# mp3thing_simple1.net
KiCad netlist of a schematic drawn in EAGLE
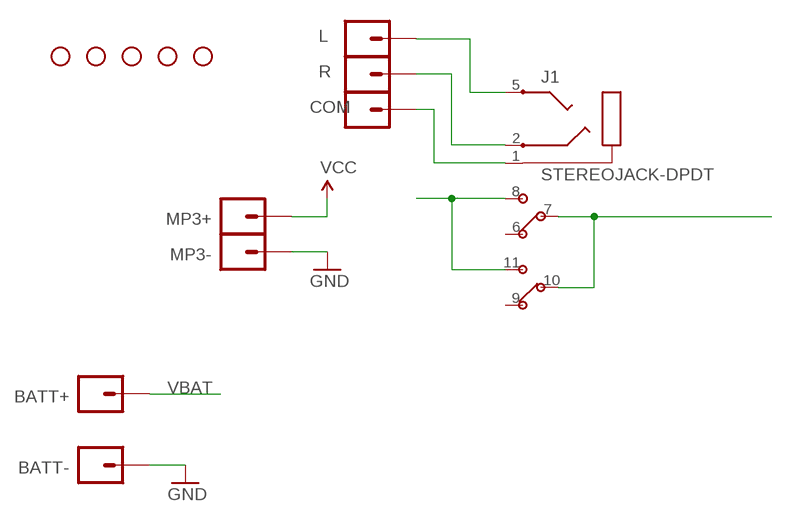
[diagram p0: schematic, sheet 1]

(export (version "E")
  (design (tool "Eeschema 10.0.6"))
  (components
    (comp (ref "BATT+")
      (value "M01PTH")
      (footprint "eagle-import:1X01")
      (libsource (lib "eagle-import") (part "M01PTH"))
    )
    (comp (ref "BATT-")
      (value "M01PTH")
      (footprint "eagle-import:1X01")
      (libsource (lib "eagle-import") (part "M01PTH"))
    )
    (comp (ref "COM")
      (value "M01PTH")
      (footprint "eagle-import:1X01")
      (libsource (lib "eagle-import") (part "M01PTH"))
    )
    (comp (ref "J1")
      (value "STEREOJACK-DPDT")
      (footprint "eagle-import:STX3100-9C")
      (libsource (lib "eagle-import") (part "STEREOJACK-DPDT"))
    )
    (comp (ref "JP1")
      (value "STAND-OFF")
      (footprint "eagle-import:STAND-OFF")
      (libsource (lib "eagle-import") (part "STAND-OFF"))
    )
    (comp (ref "JP2")
      (value "STAND-OFF")
      (footprint "eagle-import:STAND-OFF")
      (libsource (lib "eagle-import") (part "STAND-OFF"))
    )
    (comp (ref "JP3")
      (value "STAND-OFF")
      (footprint "eagle-import:STAND-OFF")
      (libsource (lib "eagle-import") (part "STAND-OFF"))
    )
    (comp (ref "JP4")
      (value "STAND-OFF")
      (footprint "eagle-import:STAND-OFF")
      (libsource (lib "eagle-import") (part "STAND-OFF"))
    )
    (comp (ref "JP5")
      (value "STAND-OFF")
      (footprint "eagle-import:STAND-OFF")
      (libsource (lib "eagle-import") (part "STAND-OFF"))
    )
    (comp (ref "L")
      (value "M01PTH")
      (footprint "eagle-import:1X01")
      (libsource (lib "eagle-import") (part "M01PTH"))
    )
    (comp (ref "MP3+")
      (value "M01PTH")
      (footprint "eagle-import:1X01")
      (libsource (lib "eagle-import") (part "M01PTH"))
    )
    (comp (ref "MP3-")
      (value "M01PTH")
      (footprint "eagle-import:1X01")
      (libsource (lib "eagle-import") (part "M01PTH"))
    )
    (comp (ref "R")
      (value "M01PTH")
      (footprint "eagle-import:1X01")
      (libsource (lib "eagle-import") (part "M01PTH"))
    )
  )
  (nets
    (net (code "1") (name "/VBAT") (class "Default")
      (node (ref "BATT+") (pin "1") (pinfunction "1_1") (pintype "passive"))
      (node (ref "J1") (pin "10") (pinfunction "10_10") (pintype "passive"))
      (node (ref "J1") (pin "7") (pinfunction "7_7") (pintype "passive"))
    )
    (net (code "2") (name "GND") (class "Default")
      (node (ref "BATT-") (pin "1") (pinfunction "1_1") (pintype "passive"))
      (node (ref "MP3-") (pin "1") (pinfunction "1_1") (pintype "passive"))
    )
    (net (code "3") (name "Net-(COM-Pad1)") (class "Default")
      (node (ref "COM") (pin "1") (pinfunction "1_1") (pintype "passive"))
      (node (ref "J1") (pin "1") (pinfunction "1_1") (pintype "passive"))
    )
    (net (code "4") (name "Net-(J1-Pad2)") (class "Default")
      (node (ref "J1") (pin "2") (pinfunction "2_2") (pintype "passive"))
      (node (ref "R") (pin "1") (pinfunction "1_1") (pintype "passive"))
    )
    (net (code "5") (name "Net-(J1-Pad5)") (class "Default")
      (node (ref "J1") (pin "5") (pinfunction "5_5") (pintype "passive"))
      (node (ref "L") (pin "1") (pinfunction "1_1") (pintype "passive"))
    )
    (net (code "6") (name "VCC") (class "Default")
      (node (ref "J1") (pin "11") (pinfunction "11_11") (pintype "passive"))
      (node (ref "J1") (pin "8") (pinfunction "8_8") (pintype "passive"))
      (node (ref "MP3+") (pin "1") (pinfunction "1_1") (pintype "passive"))
    )
    (net (code "7") (name "unconnected-(J1-Pad6)") (class "Default")
      (node (ref "J1") (pin "6") (pinfunction "6_6") (pintype "passive"))
    )
    (net (code "8") (name "unconnected-(J1-Pad9)") (class "Default")
      (node (ref "J1") (pin "9") (pinfunction "9_9") (pintype "passive"))
    )
  )
)
